# STM32_Blue_pill.net
KiCad netlist of a schematic drawn in Altium Designer
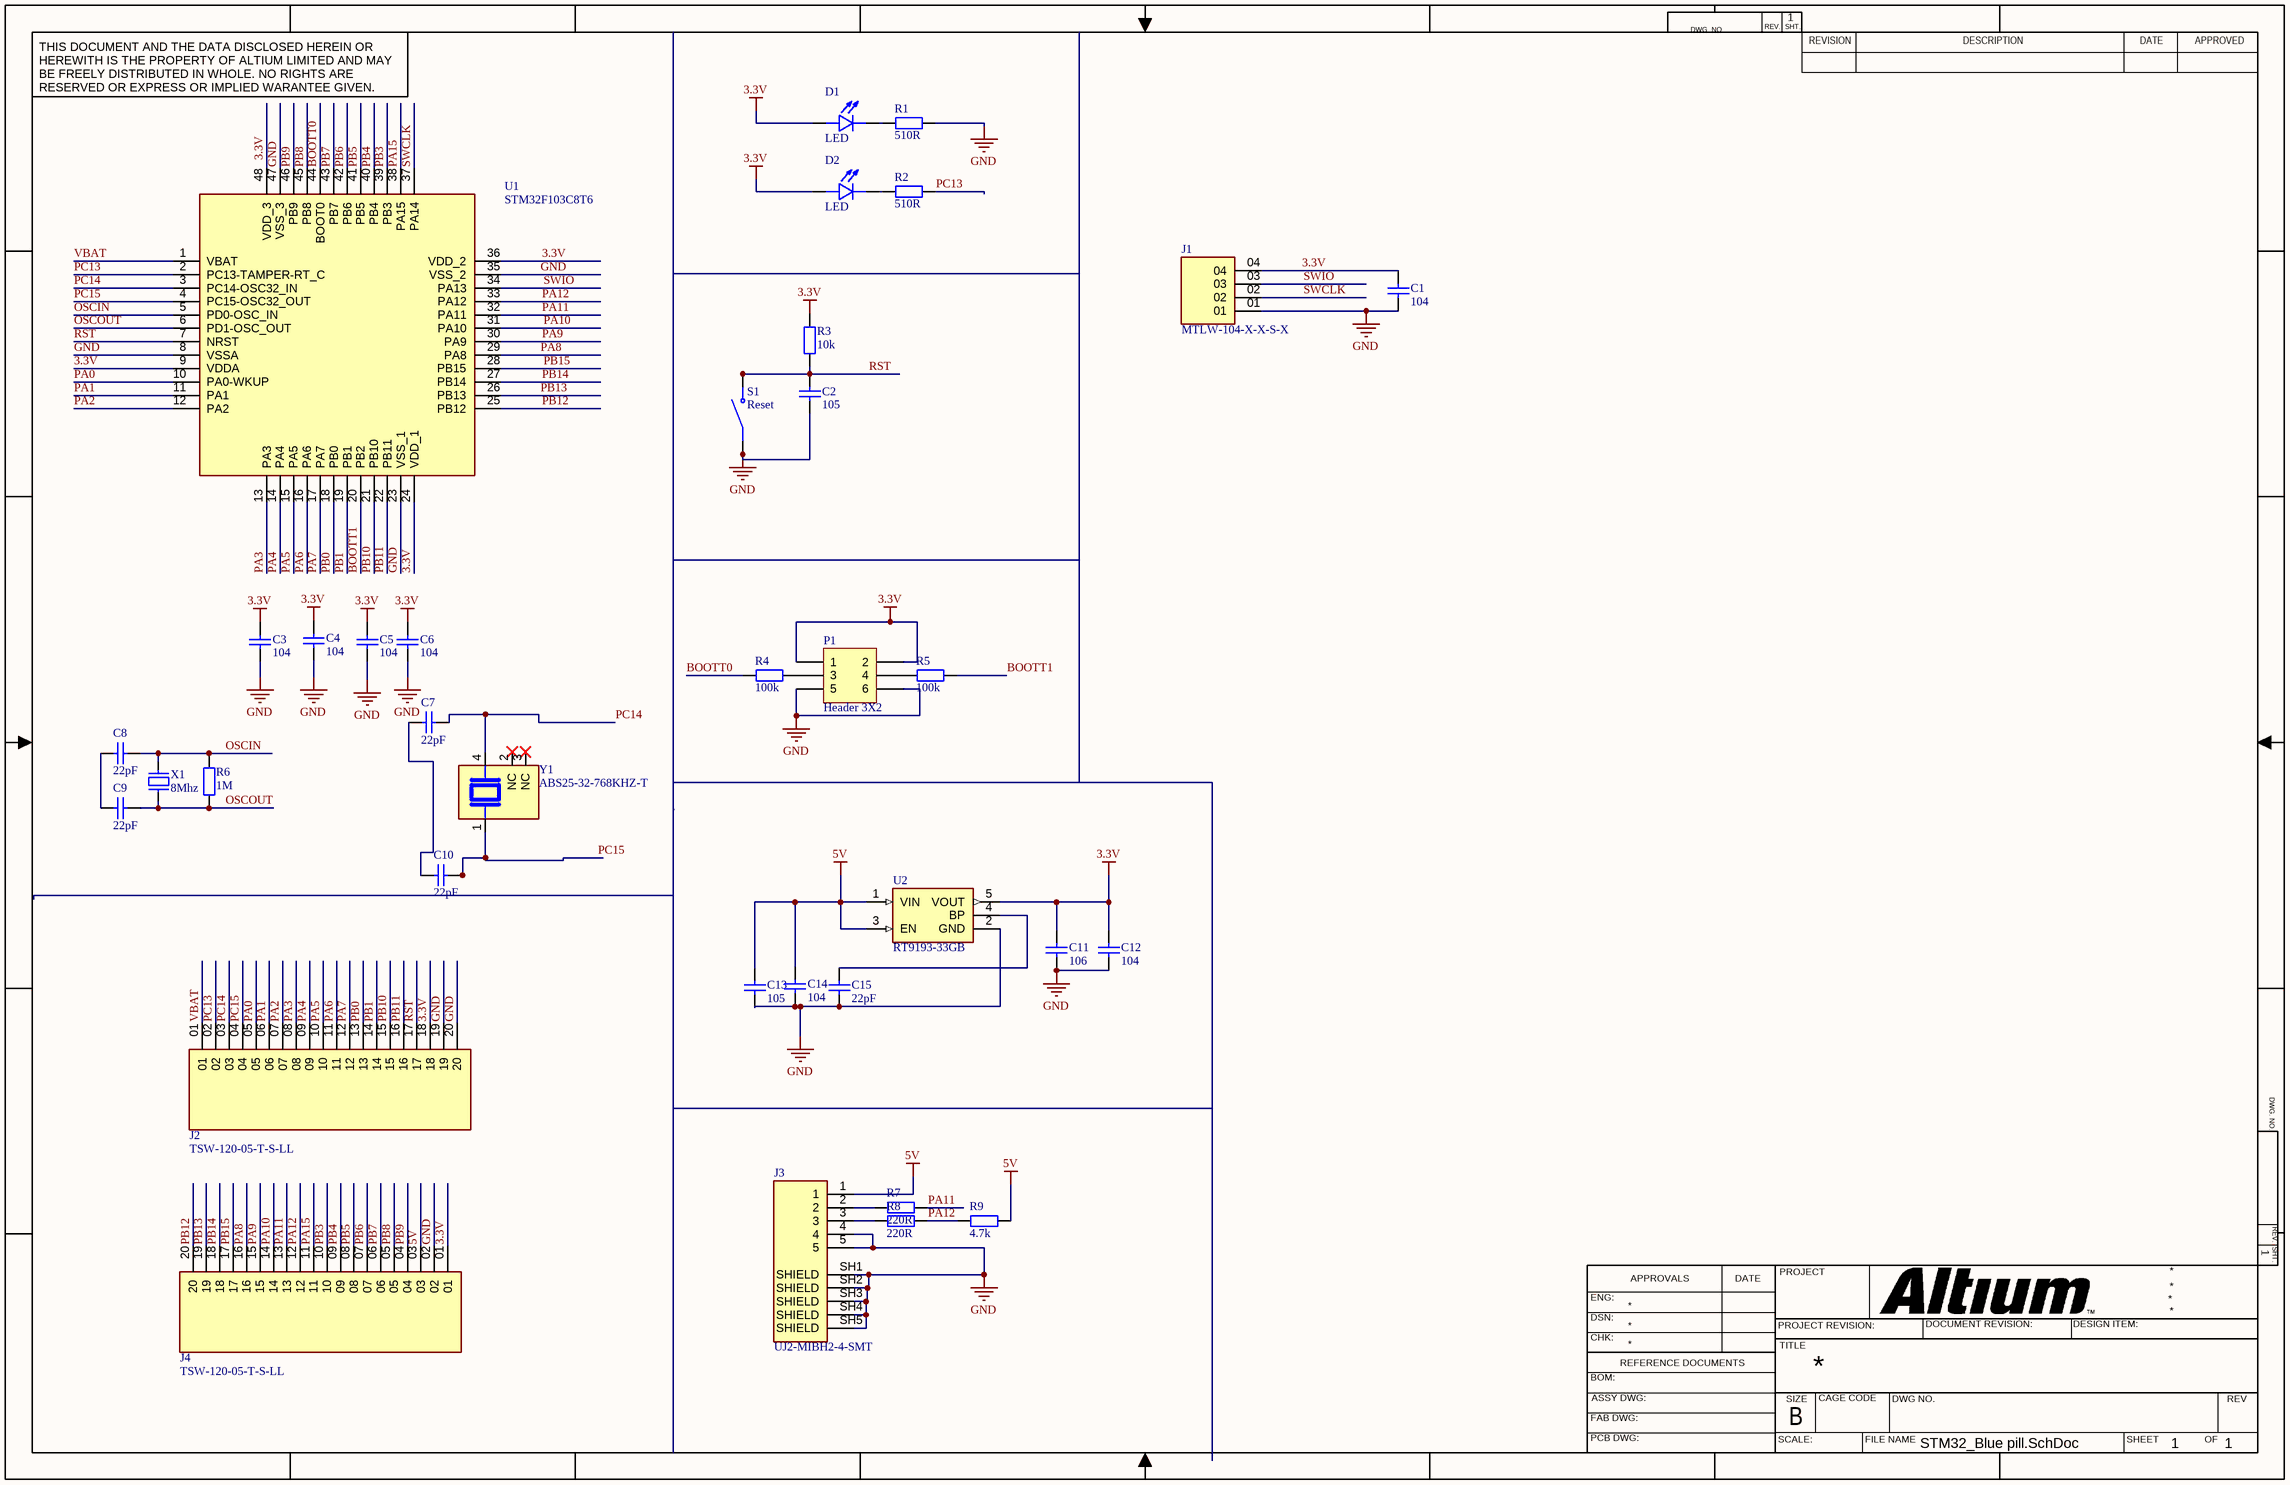
[diagram p0: STM32_Blue pill.SchDoc]

(export (version "E")
  (design (tool "Eeschema 10.0.6"))
  (components
    (comp (ref "C1")
      (value "104")
      (footprint "tu 0603")
      (description "Dán")
      (libsource (lib "Altium_Lib_by_KhueNguyenCreator") (part "Tu 0603 104 50V 10%"))
    )
    (comp (ref "C2")
      (value "105")
      (footprint "tu 0603")
      (description "Dán")
      (libsource (lib "Altium_Lib_by_KhueNguyenCreator") (part "Tu 0603 105 50V 10%"))
    )
    (comp (ref "C3")
      (value "104")
      (footprint "tu 0603")
      (description "Dán")
      (libsource (lib "Altium_Lib_by_KhueNguyenCreator") (part "Tu 0603 104 50V 10%"))
    )
    (comp (ref "C4")
      (value "104")
      (footprint "tu 0603")
      (description "Dán")
      (libsource (lib "Altium_Lib_by_KhueNguyenCreator") (part "Tu 0603 104 50V 10%"))
    )
    (comp (ref "C5")
      (value "104")
      (footprint "tu 0603")
      (description "Dán")
      (libsource (lib "Altium_Lib_by_KhueNguyenCreator") (part "Tu 0603 104 50V 10%"))
    )
    (comp (ref "C6")
      (value "104")
      (footprint "tu 0603")
      (description "Dán")
      (libsource (lib "Altium_Lib_by_KhueNguyenCreator") (part "Tu 0603 104 50V 10%"))
    )
    (comp (ref "C7")
      (value "22pF")
      (footprint "tu 0603")
      (description "Dán")
      (libsource (lib "Altium_Lib_by_KhueNguyenCreator") (part "Tu 0603 22pF 50V 10%"))
    )
    (comp (ref "C8")
      (value "22pF")
      (footprint "tu 0603")
      (description "Dán")
      (libsource (lib "Altium_Lib_by_KhueNguyenCreator") (part "Tu 0603 22pF 50V 10%"))
    )
    (comp (ref "C9")
      (value "22pF")
      (footprint "tu 0603")
      (description "Dán")
      (libsource (lib "Altium_Lib_by_KhueNguyenCreator") (part "Tu 0603 22pF 50V 10%"))
    )
    (comp (ref "C10")
      (value "22pF")
      (footprint "tu 0603")
      (description "Dán")
      (libsource (lib "Altium_Lib_by_KhueNguyenCreator") (part "Tu 0603 22pF 50V 10%"))
    )
    (comp (ref "C11")
      (value "106")
      (footprint "tu 0805")
      (description "Dán")
      (libsource (lib "Altium_Lib_by_KhueNguyenCreator") (part "Tu 0805 106 16V 10%"))
    )
    (comp (ref "C12")
      (value "104")
      (footprint "tu 0603")
      (description "Dán")
      (libsource (lib "Altium_Lib_by_KhueNguyenCreator") (part "Tu 0603 104 50V 10%"))
    )
    (comp (ref "C13")
      (value "105")
      (footprint "tu 0805")
      (description "Dán")
      (libsource (lib "Altium_Lib_by_KhueNguyenCreator") (part "Tu 0805 105 50V 10%"))
    )
    (comp (ref "C14")
      (value "104")
      (footprint "tu 0603")
      (description "Dán")
      (libsource (lib "Altium_Lib_by_KhueNguyenCreator") (part "Tu 0603 104 50V 10%"))
    )
    (comp (ref "C15")
      (value "22pF")
      (footprint "tu 0603")
      (description "Dán")
      (libsource (lib "Altium_Lib_by_KhueNguyenCreator") (part "Tu 0603 22pF 50V 10%"))
    )
    (comp (ref "D1")
      (value "LED")
      (footprint "LED_KP-1608SURCK")
      (description "LED; SMD; 0603; red; 50-150mcd; 1.6x0.8mm; 120Â°; 20mA;")
      (fields (field (name "MF") "Kingbright") (field (name "MP") "KP-1608SURCK"))
      (libsource (lib "KP-1608SURCK") (part "KP-1608SURCK"))
    )
    (comp (ref "D2")
      (value "LED")
      (footprint "LED_KP-1608SURCK")
      (description "LED; SMD; 0603; red; 50-150mcd; 1.6x0.8mm; 120Â°; 20mA;")
      (fields (field (name "MF") "Kingbright") (field (name "MP") "KP-1608SURCK"))
      (libsource (lib "KP-1608SURCK") (part "KP-1608SURCK"))
    )
    (comp (ref "J1")
      (value "MTLW-104-X-X-S-X")
      (footprint "SAMTEC_MTLW-104-X-X-S-X")
      (fields (field (name "MF") "{'manufacturer': u'Samtec Inc.'}"))
      (libsource (lib "MTLW-104-X-X-S-X") (part "MTLW-104-X-X-S-X"))
    )
    (comp (ref "J2")
      (value "TSW-120-05-T-S-LL")
      (footprint "SAMTEC_TSW-120-05-T-S-LL")
      (libsource (lib "") (part "TSW-120-05-T-S-LL_1"))
    )
    (comp (ref "J3")
      (value "UJ2-MIBH2-4-SMT")
      (footprint "CUI_UJ2-MIBH2-4-SMT")
      (description "Micro B, USB 2.0, 1.8 A, Right Angle, Surface Mount (SMT), USB Receptacle")
      (fields (field (name "MF") "CUI Devices"))
      (libsource (lib "UJ2-MIBH2-4-SMT") (part "UJ2-MIBH2-4-SMT"))
    )
    (comp (ref "J4")
      (value "TSW-120-05-T-S-LL")
      (footprint "SAMTEC_TSW-120-05-T-S-LL")
      (libsource (lib "TSW-120-05-T-S-LL") (part "TSW-120-05-T-S-LL"))
    )
    (comp (ref "P1")
      (value "Header 3X2")
      (footprint "HDR2X3")
      (description "Header, 3-Pin, Dual row")
      (fields (field (name "PUBLISHER") "Altium Limited"))
      (libsource (lib "Devzone_SCHLib") (part "Header 3X2"))
    )
    (comp (ref "R1")
      (value "510R")
      (footprint "tro smd 0603")
      (description "Dán")
      (libsource (lib "Altium_Lib_by_KhueNguyenCreator") (part "Tro 0603 5% 510R"))
    )
    (comp (ref "R2")
      (value "510R")
      (footprint "tro smd 0603")
      (description "Dán")
      (libsource (lib "Altium_Lib_by_KhueNguyenCreator") (part "Tro 0603 5% 510R"))
    )
    (comp (ref "R3")
      (value "10k")
      (footprint "tro smd 0603")
      (description "Dán")
      (libsource (lib "Altium_Lib_by_KhueNguyenCreator") (part "Tro 0603 1% 10k"))
    )
    (comp (ref "R4")
      (value "100k")
      (footprint "tro smd 0603")
      (description "Dán")
      (libsource (lib "Altium_Lib_by_KhueNguyenCreator") (part "Tro 0603 5% 100k"))
    )
    (comp (ref "R5")
      (value "100k")
      (footprint "tro smd 0603")
      (description "Dán")
      (libsource (lib "Altium_Lib_by_KhueNguyenCreator") (part "Tro 0603 5% 100k"))
    )
    (comp (ref "R6")
      (value "1M")
      (footprint "tro smd 0805")
      (description "Dán")
      (libsource (lib "Altium_Lib_by_KhueNguyenCreator") (part "Tro 0805 1% 1M"))
    )
    (comp (ref "R7")
      (value "220R")
      (footprint "tro smd 0603")
      (description "Dán")
      (libsource (lib "Altium_Lib_by_KhueNguyenCreator") (part "Tro 0603 5% 220R"))
    )
    (comp (ref "R8")
      (value "220R")
      (footprint "tro smd 0603")
      (description "Dán")
      (libsource (lib "Altium_Lib_by_KhueNguyenCreator") (part "Tro 0603 5% 220R"))
    )
    (comp (ref "R9")
      (value "4.7k")
      (footprint "tro smd 0603")
      (description "Dán")
      (libsource (lib "Altium_Lib_by_KhueNguyenCreator") (part "Tro 0603 5% 4.7k"))
    )
    (comp (ref "S1")
      (value "Reset")
      (footprint "SW_8-1437565-1")
      (fields (field (name "MP") "8-1437565-1"))
      (libsource (lib "8-1437565-1") (part "8-1437565-1"))
    )
    (comp (ref "U1")
      (value "STM32F103C8T6")
      (footprint "LQFP-48_19.6_393_58X11_SMD")
      (description "ARM® Cortex®-M3 STM32F1 Microcontroller IC 32-Bit 72MHz 64KB (64K x 8) FLASH 48-LQFP (7x7)")
      (fields (field (name "MANUFACTURER") "STMicroelectronics"))
      (libsource (lib "Altium_Lib_by_KhueNguyenCreator") (part "IC_STM32F103C8T6"))
    )
    (comp (ref "U2")
      (value "RT9193-33GB")
      (footprint "SOT94P279X129-5N")
      (description "Linear Voltage Regulator IC Positive Fixed 1 Output 300mA TSOT-23-5")
      (fields (field (name "MF") "Richtek USA") (field (name "DIGI-KEY_PART_NUMBER") "1028-1014-2-ND"))
      (libsource (lib "RT9193-33GB") (part "RT9193-33GB"))
    )
    (comp (ref "X1")
      (value "8Mhz")
      (footprint "XT2")
      (description "Crystal For all Crystal 2pin.")
      (libsource (lib "syhaunguyen") (part "XT2"))
    )
    (comp (ref "Y1")
      (value "ABS25-32-768KHZ-T")
      (footprint "XTAL_ABS25-32-768KHZ-T")
      (description "Crystal 0.032768MHz Â±20ppm (Tol) 12.5pF FUND 50000Ohm 4-Pin SMD T/R")
      (fields (field (name "MF") "Abracon"))
      (libsource (lib "ABS25-32-768KHZ-T") (part "ABS25-32-768KHZ-T"))
    )
  )
  (nets
    (net (code "1") (name "/BOOTT0") (class "Default")
      (node (ref "R4") (pin "1") (pinfunction "1_1") (pintype "passive"))
      (node (ref "U1") (pin "44") (pinfunction "BOOT0_44") (pintype "passive"))
    )
    (net (code "2") (name "/BOOTT1") (class "Default")
      (node (ref "R5") (pin "2") (pinfunction "2_2") (pintype "passive"))
      (node (ref "U1") (pin "20") (pinfunction "PB2_20") (pintype "passive"))
    )
    (net (code "3") (name "/OSCIN") (class "Default")
      (node (ref "C8") (pin "1") (pinfunction "1_1") (pintype "passive"))
      (node (ref "R6") (pin "2") (pinfunction "2_2") (pintype "passive"))
      (node (ref "U1") (pin "5") (pinfunction "PD0-OSC_IN_5") (pintype "passive"))
      (node (ref "X1") (pin "2") (pinfunction "2_2") (pintype "passive"))
    )
    (net (code "4") (name "/OSCOUT") (class "Default")
      (node (ref "C9") (pin "1") (pinfunction "1_1") (pintype "passive"))
      (node (ref "R6") (pin "1") (pinfunction "1_1") (pintype "passive"))
      (node (ref "U1") (pin "6") (pinfunction "PD1-OSC_OUT_6") (pintype "passive"))
      (node (ref "X1") (pin "1") (pinfunction "1_1") (pintype "passive"))
    )
    (net (code "5") (name "/PA0") (class "Default")
      (node (ref "J2") (pin "05") (pinfunction "05_05") (pintype "passive"))
      (node (ref "U1") (pin "10") (pinfunction "PA0-WKUP_10") (pintype "passive"))
    )
    (net (code "6") (name "/PA1") (class "Default")
      (node (ref "J2") (pin "06") (pinfunction "06_06") (pintype "passive"))
      (node (ref "U1") (pin "11") (pinfunction "PA1_11") (pintype "passive"))
    )
    (net (code "7") (name "/PA2") (class "Default")
      (node (ref "J2") (pin "07") (pinfunction "07_07") (pintype "passive"))
      (node (ref "U1") (pin "12") (pinfunction "PA2_12") (pintype "passive"))
    )
    (net (code "8") (name "/PA3") (class "Default")
      (node (ref "J2") (pin "08") (pinfunction "08_08") (pintype "passive"))
      (node (ref "U1") (pin "13") (pinfunction "PA3_13") (pintype "passive"))
    )
    (net (code "9") (name "/PA4") (class "Default")
      (node (ref "J2") (pin "09") (pinfunction "09_09") (pintype "passive"))
      (node (ref "U1") (pin "14") (pinfunction "PA4_14") (pintype "passive"))
    )
    (net (code "10") (name "/PA5") (class "Default")
      (node (ref "J2") (pin "10") (pinfunction "10_10") (pintype "passive"))
      (node (ref "U1") (pin "15") (pinfunction "PA5_15") (pintype "passive"))
    )
    (net (code "11") (name "/PA6") (class "Default")
      (node (ref "J2") (pin "11") (pinfunction "11_11") (pintype "passive"))
      (node (ref "U1") (pin "16") (pinfunction "PA6_16") (pintype "passive"))
    )
    (net (code "12") (name "/PA7") (class "Default")
      (node (ref "J2") (pin "12") (pinfunction "12_12") (pintype "passive"))
      (node (ref "U1") (pin "17") (pinfunction "PA7_17") (pintype "passive"))
    )
    (net (code "13") (name "/PA8") (class "Default")
      (node (ref "J4") (pin "16") (pinfunction "16_16") (pintype "passive"))
      (node (ref "U1") (pin "29") (pinfunction "PA8_29") (pintype "passive"))
    )
    (net (code "14") (name "/PA9") (class "Default")
      (node (ref "J4") (pin "15") (pinfunction "15_15") (pintype "passive"))
      (node (ref "U1") (pin "30") (pinfunction "PA9_30") (pintype "passive"))
    )
    (net (code "15") (name "/PA10") (class "Default")
      (node (ref "J4") (pin "14") (pinfunction "14_14") (pintype "passive"))
      (node (ref "U1") (pin "31") (pinfunction "PA10_31") (pintype "passive"))
    )
    (net (code "16") (name "/PA11") (class "Default")
      (node (ref "J4") (pin "13") (pinfunction "13_13") (pintype "passive"))
      (node (ref "R7") (pin "2") (pinfunction "2_2") (pintype "passive"))
      (node (ref "U1") (pin "32") (pinfunction "PA11_32") (pintype "passive"))
    )
    (net (code "17") (name "/PA12") (class "Default")
      (node (ref "J4") (pin "12") (pinfunction "12_12") (pintype "passive"))
      (node (ref "R8") (pin "2") (pinfunction "2_2") (pintype "passive"))
      (node (ref "R9") (pin "1") (pinfunction "1_1") (pintype "passive"))
      (node (ref "U1") (pin "33") (pinfunction "PA12_33") (pintype "passive"))
    )
    (net (code "18") (name "/PA15") (class "Default")
      (node (ref "J4") (pin "11") (pinfunction "11_11") (pintype "passive"))
      (node (ref "U1") (pin "38") (pinfunction "PA15_38") (pintype "passive"))
    )
    (net (code "19") (name "/PB0") (class "Default")
      (node (ref "J2") (pin "13") (pinfunction "13_13") (pintype "passive"))
      (node (ref "U1") (pin "18") (pinfunction "PB0_18") (pintype "passive"))
    )
    (net (code "20") (name "/PB1") (class "Default")
      (node (ref "J2") (pin "14") (pinfunction "14_14") (pintype "passive"))
      (node (ref "U1") (pin "19") (pinfunction "PB1_19") (pintype "passive"))
    )
    (net (code "21") (name "/PB3") (class "Default")
      (node (ref "J4") (pin "10") (pinfunction "10_10") (pintype "passive"))
      (node (ref "U1") (pin "39") (pinfunction "PB3_39") (pintype "passive"))
    )
    (net (code "22") (name "/PB4") (class "Default")
      (node (ref "J4") (pin "09") (pinfunction "09_09") (pintype "passive"))
      (node (ref "U1") (pin "40") (pinfunction "PB4_40") (pintype "passive"))
    )
    (net (code "23") (name "/PB5") (class "Default")
      (node (ref "J4") (pin "08") (pinfunction "08_08") (pintype "passive"))
      (node (ref "U1") (pin "41") (pinfunction "PB5_41") (pintype "passive"))
    )
    (net (code "24") (name "/PB6") (class "Default")
      (node (ref "J4") (pin "07") (pinfunction "07_07") (pintype "passive"))
      (node (ref "U1") (pin "42") (pinfunction "PB6_42") (pintype "passive"))
    )
    (net (code "25") (name "/PB7") (class "Default")
      (node (ref "J4") (pin "06") (pinfunction "06_06") (pintype "passive"))
      (node (ref "U1") (pin "43") (pinfunction "PB7_43") (pintype "passive"))
    )
    (net (code "26") (name "/PB8") (class "Default")
      (node (ref "J4") (pin "05") (pinfunction "05_05") (pintype "passive"))
      (node (ref "U1") (pin "45") (pinfunction "PB8_45") (pintype "passive"))
    )
    (net (code "27") (name "/PB9") (class "Default")
      (node (ref "J4") (pin "04") (pinfunction "04_04") (pintype "passive"))
      (node (ref "U1") (pin "46") (pinfunction "PB9_46") (pintype "passive"))
    )
    (net (code "28") (name "/PB10") (class "Default")
      (node (ref "J2") (pin "15") (pinfunction "15_15") (pintype "passive"))
      (node (ref "U1") (pin "21") (pinfunction "PB10_21") (pintype "passive"))
    )
    (net (code "29") (name "/PB11") (class "Default")
      (node (ref "J2") (pin "16") (pinfunction "16_16") (pintype "passive"))
      (node (ref "U1") (pin "22") (pinfunction "PB11_22") (pintype "passive"))
    )
    (net (code "30") (name "/PB12") (class "Default")
      (node (ref "J4") (pin "20") (pinfunction "20_20") (pintype "passive"))
      (node (ref "U1") (pin "25") (pinfunction "PB12_25") (pintype "passive"))
    )
    (net (code "31") (name "/PB13") (class "Default")
      (node (ref "J4") (pin "19") (pinfunction "19_19") (pintype "passive"))
      (node (ref "U1") (pin "26") (pinfunction "PB13_26") (pintype "passive"))
    )
    (net (code "32") (name "/PB14") (class "Default")
      (node (ref "J4") (pin "18") (pinfunction "18_18") (pintype "passive"))
      (node (ref "U1") (pin "27") (pinfunction "PB14_27") (pintype "passive"))
    )
    (net (code "33") (name "/PB15") (class "Default")
      (node (ref "J4") (pin "17") (pinfunction "17_17") (pintype "passive"))
      (node (ref "U1") (pin "28") (pinfunction "PB15_28") (pintype "passive"))
    )
    (net (code "34") (name "/PC13") (class "Default")
      (node (ref "J2") (pin "02") (pinfunction "02_02") (pintype "passive"))
      (node (ref "R2") (pin "2") (pinfunction "2_2") (pintype "passive"))
      (node (ref "U1") (pin "2") (pinfunction "PC13-TAMPER-RT_C_2") (pintype "passive"))
    )
    (net (code "35") (name "/PC14") (class "Default")
      (node (ref "C7") (pin "1") (pinfunction "1_1") (pintype "passive"))
      (node (ref "J2") (pin "03") (pinfunction "03_03") (pintype "passive"))
      (node (ref "U1") (pin "3") (pinfunction "PC14-OSC32_IN_3") (pintype "passive"))
      (node (ref "Y1") (pin "4") (pinfunction "2_4") (pintype "passive"))
    )
    (net (code "36") (name "/PC15") (class "Default")
      (node (ref "C10") (pin "1") (pinfunction "1_1") (pintype "passive"))
      (node (ref "J2") (pin "04") (pinfunction "04_04") (pintype "passive"))
      (node (ref "U1") (pin "4") (pinfunction "PC15-OSC32_OUT_4") (pintype "passive"))
      (node (ref "Y1") (pin "1") (pinfunction "1_1") (pintype "passive"))
    )
    (net (code "37") (name "/RST") (class "Default")
      (node (ref "C2") (pin "1") (pinfunction "1_1") (pintype "passive"))
      (node (ref "J2") (pin "17") (pinfunction "17_17") (pintype "passive"))
      (node (ref "R3") (pin "1") (pinfunction "1_1") (pintype "passive"))
      (node (ref "S1") (pin "3") (pinfunction "NO_3") (pintype "passive"))
      (node (ref "S1") (pin "4") (pinfunction "NO_4") (pintype "passive"))
      (node (ref "U1") (pin "7") (pinfunction "NRST_7") (pintype "passive"))
    )
    (net (code "38") (name "/SWCLK") (class "Default")
      (node (ref "J1") (pin "02") (pinfunction "02_02") (pintype "passive"))
      (node (ref "U1") (pin "37") (pinfunction "PA14_37") (pintype "passive"))
    )
    (net (code "39") (name "/SWIO") (class "Default")
      (node (ref "J1") (pin "03") (pinfunction "03_03") (pintype "passive"))
      (node (ref "U1") (pin "34") (pinfunction "PA13_34") (pintype "passive"))
    )
    (net (code "40") (name "/VBAT") (class "Default")
      (node (ref "J2") (pin "01") (pinfunction "01_01") (pintype "passive"))
      (node (ref "U1") (pin "1") (pinfunction "VBAT_1") (pintype "passive"))
    )
    (net (code "41") (name "3.3V") (class "Default")
      (node (ref "C1") (pin "1") (pinfunction "1_1") (pintype "passive"))
      (node (ref "C11") (pin "1") (pinfunction "1_1") (pintype "passive"))
      (node (ref "C12") (pin "1") (pinfunction "1_1") (pintype "passive"))
      (node (ref "C3") (pin "1") (pinfunction "1_1") (pintype "passive"))
      (node (ref "C4") (pin "1") (pinfunction "1_1") (pintype "passive"))
      (node (ref "C5") (pin "1") (pinfunction "1_1") (pintype "passive"))
      (node (ref "C6") (pin "1") (pinfunction "1_1") (pintype "passive"))
      (node (ref "D1") (pin "1") (pinfunction "A_1") (pintype "passive"))
      (node (ref "D2") (pin "1") (pinfunction "A_1") (pintype "passive"))
      (node (ref "J1") (pin "04") (pinfunction "04_04") (pintype "passive"))
      (node (ref "J2") (pin "18") (pinfunction "18_18") (pintype "passive"))
      (node (ref "J4") (pin "01") (pinfunction "01_01") (pintype "passive"))
      (node (ref "P1") (pin "1") (pinfunction "1_1") (pintype "passive"))
      (node (ref "P1") (pin "2") (pinfunction "2_2") (pintype "passive"))
      (node (ref "R3") (pin "2") (pinfunction "2_2") (pintype "passive"))
      (node (ref "U1") (pin "24") (pinfunction "VDD_1_24") (pintype "passive"))
      (node (ref "U1") (pin "36") (pinfunction "VDD_2_36") (pintype "passive"))
      (node (ref "U1") (pin "48") (pinfunction "VDD_3_48") (pintype "passive"))
      (node (ref "U1") (pin "9") (pinfunction "VDDA_9") (pintype "passive"))
      (node (ref "U2") (pin "5") (pinfunction "VOUT_5") (pintype "output"))
    )
    (net (code "42") (name "5V") (class "Default")
      (node (ref "C13") (pin "1") (pinfunction "1_1") (pintype "passive"))
      (node (ref "C14") (pin "1") (pinfunction "1_1") (pintype "passive"))
      (node (ref "J3") (pin "1") (pinfunction "1_1") (pintype "passive"))
      (node (ref "J4") (pin "03") (pinfunction "03_03") (pintype "passive"))
      (node (ref "R9") (pin "2") (pinfunction "2_2") (pintype "passive"))
      (node (ref "U2") (pin "1") (pinfunction "VIN_1") (pintype "input"))
      (node (ref "U2") (pin "3") (pinfunction "EN_3") (pintype "input"))
    )
    (net (code "43") (name "GND") (class "Default")
      (node (ref "C1") (pin "2") (pinfunction "2_2") (pintype "passive"))
      (node (ref "C11") (pin "2") (pinfunction "2_2") (pintype "passive"))
      (node (ref "C12") (pin "2") (pinfunction "2_2") (pintype "passive"))
      (node (ref "C13") (pin "2") (pinfunction "2_2") (pintype "passive"))
      (node (ref "C14") (pin "2") (pinfunction "2_2") (pintype "passive"))
      (node (ref "C15") (pin "2") (pinfunction "2_2") (pintype "passive"))
      (node (ref "C2") (pin "2") (pinfunction "2_2") (pintype "passive"))
      (node (ref "C3") (pin "2") (pinfunction "2_2") (pintype "passive"))
      (node (ref "C4") (pin "2") (pinfunction "2_2") (pintype "passive"))
      (node (ref "C5") (pin "2") (pinfunction "2_2") (pintype "passive"))
      (node (ref "C6") (pin "2") (pinfunction "2_2") (pintype "passive"))
      (node (ref "J1") (pin "01") (pinfunction "01_01") (pintype "passive"))
      (node (ref "J2") (pin "19") (pinfunction "19_19") (pintype "passive"))
      (node (ref "J2") (pin "20") (pinfunction "20_20") (pintype "passive"))
      (node (ref "J3") (pin "4") (pinfunction "4_4") (pintype "passive"))
      (node (ref "J3") (pin "5") (pinfunction "5_5") (pintype "passive"))
      (node (ref "J3") (pin "SH1") (pinfunction "SHIELD_SH1") (pintype "passive"))
      (node (ref "J3") (pin "SH2") (pinfunction "SHIELD_SH2") (pintype "passive"))
      (node (ref "J3") (pin "SH3") (pinfunction "SHIELD_SH3") (pintype "passive"))
      (node (ref "J3") (pin "SH4") (pinfunction "SHIELD_SH4") (pintype "passive"))
      (node (ref "J3") (pin "SH5") (pinfunction "SHIELD_SH5") (pintype "passive"))
      (node (ref "J4") (pin "02") (pinfunction "02_02") (pintype "passive"))
      (node (ref "P1") (pin "5") (pinfunction "5_5") (pintype "passive"))
      (node (ref "P1") (pin "6") (pinfunction "6_6") (pintype "passive"))
      (node (ref "R1") (pin "2") (pinfunction "2_2") (pintype "passive"))
      (node (ref "S1") (pin "1") (pinfunction "COM_1") (pintype "passive"))
      (node (ref "S1") (pin "2") (pinfunction "COM_2") (pintype "passive"))
      (node (ref "U1") (pin "23") (pinfunction "VSS_1_23") (pintype "passive"))
      (node (ref "U1") (pin "35") (pinfunction "VSS_2_35") (pintype "passive"))
      (node (ref "U1") (pin "47") (pinfunction "VSS_3_47") (pintype "passive"))
      (node (ref "U1") (pin "8") (pinfunction "VSSA_8") (pintype "passive"))
      (node (ref "U2") (pin "2") (pinfunction "GND_2") (pintype "power_in"))
    )
    (net (code "44") (name "Net-(C8-Pad2)") (class "Default")
      (node (ref "C8") (pin "2") (pinfunction "2_2") (pintype "passive"))
      (node (ref "C9") (pin "2") (pinfunction "2_2") (pintype "passive"))
    )
    (net (code "45") (name "Net-(C10-Pad2)") (class "Default")
      (node (ref "C10") (pin "2") (pinfunction "2_2") (pintype "passive"))
      (node (ref "C7") (pin "2") (pinfunction "2_2") (pintype "passive"))
    )
    (net (code "46") (name "Net-(D1-C)") (class "Default")
      (node (ref "D1") (pin "2") (pinfunction "C_2") (pintype "passive"))
      (node (ref "R1") (pin "1") (pinfunction "1_1") (pintype "passive"))
    )
    (net (code "47") (name "Net-(D2-C)") (class "Default")
      (node (ref "D2") (pin "2") (pinfunction "C_2") (pintype "passive"))
      (node (ref "R2") (pin "1") (pinfunction "1_1") (pintype "passive"))
    )
    (net (code "48") (name "Net-(J3-Pad2)") (class "Default")
      (node (ref "J3") (pin "2") (pinfunction "2_2") (pintype "passive"))
      (node (ref "R7") (pin "1") (pinfunction "1_1") (pintype "passive"))
    )
    (net (code "49") (name "Net-(J3-Pad3)") (class "Default")
      (node (ref "J3") (pin "3") (pinfunction "3_3") (pintype "passive"))
      (node (ref "R8") (pin "1") (pinfunction "1_1") (pintype "passive"))
    )
    (net (code "50") (name "Net-(P1-Pad3)") (class "Default")
      (node (ref "P1") (pin "3") (pinfunction "3_3") (pintype "passive"))
      (node (ref "R4") (pin "2") (pinfunction "2_2") (pintype "passive"))
    )
    (net (code "51") (name "Net-(P1-Pad4)") (class "Default")
      (node (ref "P1") (pin "4") (pinfunction "4_4") (pintype "passive"))
      (node (ref "R5") (pin "1") (pinfunction "1_1") (pintype "passive"))
    )
    (net (code "52") (name "Net-(U2-BP)") (class "Default")
      (node (ref "C15") (pin "1") (pinfunction "1_1") (pintype "passive"))
      (node (ref "U2") (pin "4") (pinfunction "BP_4") (pintype "passive"))
    )
    (net (code "53") (name "unconnected-(Y1-NC-Pad2)") (class "Default")
      (node (ref "Y1") (pin "2") (pinfunction "NC_2") (pintype "passive+no_connect"))
    )
    (net (code "54") (name "unconnected-(Y1-NC-Pad3)") (class "Default")
      (node (ref "Y1") (pin "3") (pinfunction "NC_3") (pintype "passive+no_connect"))
    )
  )
)
